# uno_shield_generic_1.net
KiCad netlist of a schematic drawn in EAGLE
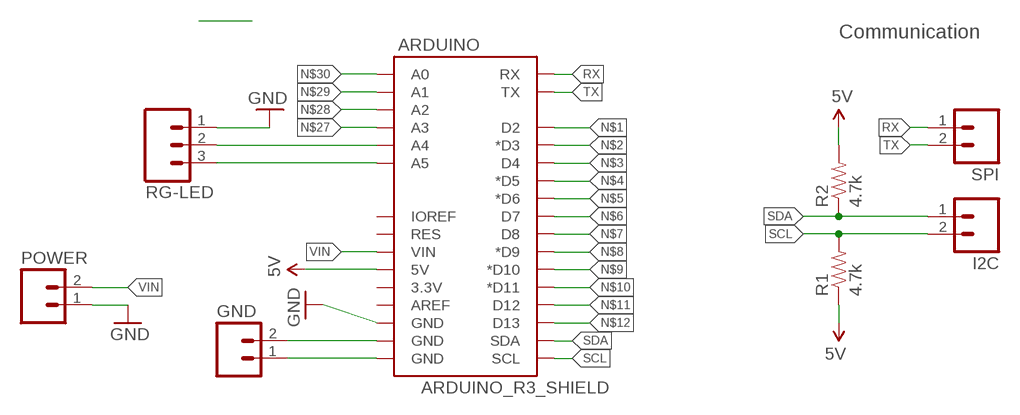
[diagram p0: schematic, sheet 1]

(export (version "E")
  (design (tool "Eeschema 10.0.6"))
  (components
    (comp (ref "ARDUINO")
      (value "ARDUINO_R3_SHIELD")
      (footprint "eagle-import:UNO_R3_SHIELD")
      (libsource (lib "eagle-import") (part "ARDUINO_R3_SHIELD"))
    )
    (comp (ref "GND")
      (value "M02LOCK_LONGPADS")
      (footprint "eagle-import:1X02_LOCK_LONGPADS")
      (libsource (lib "eagle-import") (part "M02LOCK_LONGPADS"))
    )
    (comp (ref "I2C")
      (value "M02LOCK_LONGPADS")
      (footprint "eagle-import:1X02_LOCK_LONGPADS")
      (libsource (lib "eagle-import") (part "M02LOCK_LONGPADS"))
    )
    (comp (ref "POWER")
      (value "M02LOCK_LONGPADS")
      (footprint "eagle-import:1X02_LOCK_LONGPADS")
      (libsource (lib "eagle-import") (part "M02LOCK_LONGPADS"))
    )
    (comp (ref "R1")
      (value "4.7k")
      (footprint "eagle-import:AXIAL-0.3-KIT")
      (libsource (lib "eagle-import") (part "RESISTORKIT"))
    )
    (comp (ref "R2")
      (value "4.7k")
      (footprint "eagle-import:AXIAL-0.3-KIT")
      (libsource (lib "eagle-import") (part "RESISTORKIT"))
    )
    (comp (ref "RG-LED")
      (value "M03LONGPADS")
      (footprint "eagle-import:1X03_LONGPADS")
      (libsource (lib "eagle-import") (part "M03LONGPADS"))
    )
    (comp (ref "SPI")
      (value "M02LOCK_LONGPADS")
      (footprint "eagle-import:1X02_LOCK_LONGPADS")
      (libsource (lib "eagle-import") (part "M02LOCK_LONGPADS"))
    )
  )
  (nets
    (net (code "1") (name "5V") (class "Default")
      (node (ref "ARDUINO") (pin "5V") (pinfunction "5V_5V") (pintype "bidirectional"))
      (node (ref "R1") (pin "P$1") (pinfunction "1_P$1") (pintype "passive"))
      (node (ref "R2") (pin "P$2") (pinfunction "2_P$2") (pintype "passive"))
    )
    (net (code "2") (name "GND") (class "Default")
      (node (ref "ARDUINO") (pin "GND@2") (pinfunction "GND_GND@2") (pintype "bidirectional"))
      (node (ref "POWER") (pin "1") (pinfunction "1_1") (pintype "passive"))
      (node (ref "RG-LED") (pin "1") (pinfunction "1_1") (pintype "passive"))
    )
    (net (code "3") (name "N$1") (class "Default")
      (node (ref "ARDUINO") (pin "D2") (pinfunction "D2_D2") (pintype "bidirectional"))
    )
    (net (code "4") (name "N$2") (class "Default")
      (node (ref "ARDUINO") (pin "D3") (pinfunction "*D3_D3") (pintype "bidirectional"))
    )
    (net (code "5") (name "N$3") (class "Default")
      (node (ref "ARDUINO") (pin "D4") (pinfunction "D4_D4") (pintype "bidirectional"))
    )
    (net (code "6") (name "N$4") (class "Default")
      (node (ref "ARDUINO") (pin "D5") (pinfunction "*D5_D5") (pintype "bidirectional"))
    )
    (net (code "7") (name "N$5") (class "Default")
      (node (ref "ARDUINO") (pin "D6") (pinfunction "*D6_D6") (pintype "bidirectional"))
    )
    (net (code "8") (name "N$6") (class "Default")
      (node (ref "ARDUINO") (pin "D7") (pinfunction "D7_D7") (pintype "bidirectional"))
    )
    (net (code "9") (name "N$7") (class "Default")
      (node (ref "ARDUINO") (pin "D8") (pinfunction "D8_D8") (pintype "bidirectional"))
    )
    (net (code "10") (name "N$8") (class "Default")
      (node (ref "ARDUINO") (pin "D9") (pinfunction "*D9_D9") (pintype "bidirectional"))
    )
    (net (code "11") (name "N$9") (class "Default")
      (node (ref "ARDUINO") (pin "D10") (pinfunction "*D10_D10") (pintype "bidirectional"))
    )
    (net (code "12") (name "N$10") (class "Default")
      (node (ref "ARDUINO") (pin "D11") (pinfunction "*D11_D11") (pintype "bidirectional"))
    )
    (net (code "13") (name "N$11") (class "Default")
      (node (ref "ARDUINO") (pin "D12") (pinfunction "D12_D12") (pintype "bidirectional"))
    )
    (net (code "14") (name "N$12") (class "Default")
      (node (ref "ARDUINO") (pin "D13") (pinfunction "D13_D13") (pintype "bidirectional"))
    )
    (net (code "15") (name "N$27") (class "Default")
      (node (ref "ARDUINO") (pin "A3") (pinfunction "A3_A3") (pintype "bidirectional"))
    )
    (net (code "16") (name "N$28") (class "Default")
      (node (ref "ARDUINO") (pin "A2") (pinfunction "A2_A2") (pintype "bidirectional"))
    )
    (net (code "17") (name "N$29") (class "Default")
      (node (ref "ARDUINO") (pin "A1") (pinfunction "A1_A1") (pintype "bidirectional"))
    )
    (net (code "18") (name "N$30") (class "Default")
      (node (ref "ARDUINO") (pin "A0") (pinfunction "A0_A0") (pintype "bidirectional"))
    )
    (net (code "19") (name "Net-(ARDUINO-GND-PadGND@0)") (class "Default")
      (node (ref "ARDUINO") (pin "GND@0") (pinfunction "GND_GND@0") (pintype "bidirectional"))
      (node (ref "GND") (pin "1") (pinfunction "1_1") (pintype "passive"))
    )
    (net (code "20") (name "Net-(ARDUINO-GND-PadGND@1)") (class "Default")
      (node (ref "ARDUINO") (pin "GND@1") (pinfunction "GND_GND@1") (pintype "bidirectional"))
      (node (ref "GND") (pin "2") (pinfunction "2_2") (pintype "passive"))
    )
    (net (code "21") (name "Net-(ARDUINO-PadA4)") (class "Default")
      (node (ref "ARDUINO") (pin "A4") (pinfunction "A4_A4") (pintype "bidirectional"))
      (node (ref "RG-LED") (pin "2") (pinfunction "2_2") (pintype "passive"))
    )
    (net (code "22") (name "Net-(ARDUINO-PadA5)") (class "Default")
      (node (ref "ARDUINO") (pin "A5") (pinfunction "A5_A5") (pintype "bidirectional"))
      (node (ref "RG-LED") (pin "3") (pinfunction "3_3") (pintype "passive"))
    )
    (net (code "23") (name "RX") (class "Default")
      (node (ref "ARDUINO") (pin "RX") (pinfunction "RX_RX") (pintype "bidirectional"))
      (node (ref "SPI") (pin "1") (pinfunction "1_1") (pintype "passive"))
    )
    (net (code "24") (name "SCL") (class "Default")
      (node (ref "ARDUINO") (pin "SCL") (pinfunction "SCL_SCL") (pintype "bidirectional"))
      (node (ref "I2C") (pin "2") (pinfunction "2_2") (pintype "passive"))
      (node (ref "R1") (pin "P$2") (pinfunction "2_P$2") (pintype "passive"))
    )
    (net (code "25") (name "SDA") (class "Default")
      (node (ref "ARDUINO") (pin "SDA") (pinfunction "SDA_SDA") (pintype "bidirectional"))
      (node (ref "I2C") (pin "1") (pinfunction "1_1") (pintype "passive"))
      (node (ref "R2") (pin "P$1") (pinfunction "1_P$1") (pintype "passive"))
    )
    (net (code "26") (name "TX") (class "Default")
      (node (ref "ARDUINO") (pin "TX") (pinfunction "TX_TX") (pintype "bidirectional"))
      (node (ref "SPI") (pin "2") (pinfunction "2_2") (pintype "passive"))
    )
    (net (code "27") (name "VIN") (class "Default")
      (node (ref "ARDUINO") (pin "VIN") (pinfunction "VIN_VIN") (pintype "bidirectional"))
      (node (ref "POWER") (pin "2") (pinfunction "2_2") (pintype "passive"))
    )
    (net (code "28") (name "unconnected-(ARDUINO-Pad3.3V)") (class "Default")
      (node (ref "ARDUINO") (pin "3.3V") (pinfunction "3.3V_3.3V") (pintype "bidirectional"))
    )
    (net (code "29") (name "unconnected-(ARDUINO-PadAREF)") (class "Default")
      (node (ref "ARDUINO") (pin "AREF") (pinfunction "AREF_AREF") (pintype "bidirectional"))
    )
    (net (code "30") (name "unconnected-(ARDUINO-PadIOREF)") (class "Default")
      (node (ref "ARDUINO") (pin "IOREF") (pinfunction "IOREF_IOREF") (pintype "bidirectional"))
    )
    (net (code "31") (name "unconnected-(ARDUINO-PadRES)") (class "Default")
      (node (ref "ARDUINO") (pin "RES") (pinfunction "RES_RES") (pintype "bidirectional"))
    )
  )
)
